# Sheet2.net
KiCad netlist of a schematic drawn in Altium Designer
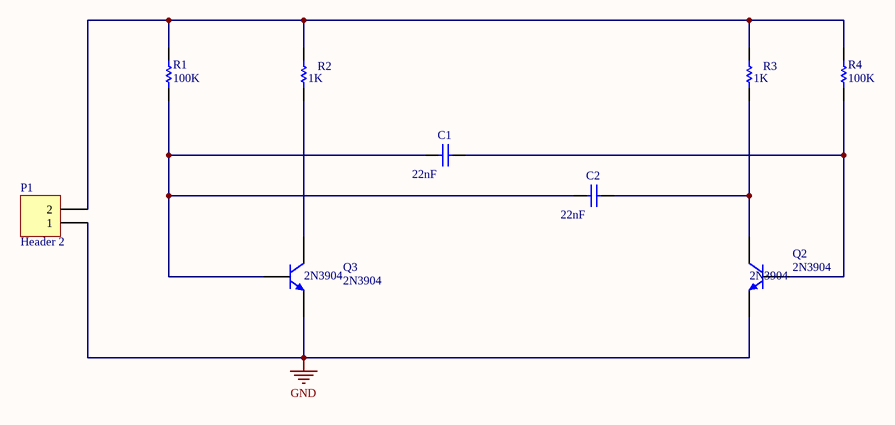
[diagram p0: Sheet2.SchDoc]

(export (version "E")
  (design (tool "Eeschema 10.0.6"))
  (components
    (comp (ref "C1")
      (value "22nF")
      (footprint "CAP1206")
      (description "TOTAL CAPACITOR SMD PACK")
      (fields (field (name "DESIGNER") "Abbas Basereh"))
      (libsource (lib "Altium") (part "CAP SMD PACKAGE"))
    )
    (comp (ref "C2")
      (value "22nF")
      (footprint "CAP1206")
      (description "TOTAL CAPACITOR SMD PACK")
      (fields (field (name "DESIGNER") "Abbas Basereh"))
      (libsource (lib "Altium") (part "CAP SMD PACKAGE"))
    )
    (comp (ref "P1")
      (value "Header 2")
      (footprint "HDR1X2")
      (description "Header, 2-Pin")
      (fields (field (name "PUBLISHER") "Altium Limited"))
      (libsource (lib "Altium") (part "Header 2"))
    )
    (comp (ref "Q2")
      (value "2N3904")
      (footprint "2N3904")
      (description "NPN Transistor")
      (libsource (lib "Altium") (part "2N3904"))
    )
    (comp (ref "Q3")
      (value "2N3904")
      (footprint "2N3904")
      (description "NPN Transistor")
      (libsource (lib "Altium") (part "2N3904"))
    )
    (comp (ref "R1")
      (value "100K")
      (footprint "RES1206")
      (description "TOTAL SMD RESISTOR PACK")
      (fields (field (name "DESIGNER") "Abbas Basereh"))
      (libsource (lib "Altium") (part "RES SMD PACKAGE"))
    )
    (comp (ref "R2")
      (value "1K")
      (footprint "RES1206")
      (description "TOTAL SMD RESISTOR PACK")
      (fields (field (name "DESIGNER") "Abbas Basereh"))
      (libsource (lib "Altium") (part "RES SMD PACKAGE"))
    )
    (comp (ref "R3")
      (value "1K")
      (footprint "RES1206")
      (description "TOTAL SMD RESISTOR PACK")
      (fields (field (name "DESIGNER") "Abbas Basereh"))
      (libsource (lib "Altium") (part "RES SMD PACKAGE"))
    )
    (comp (ref "R4")
      (value "100K")
      (footprint "RES1206")
      (description "TOTAL SMD RESISTOR PACK")
      (fields (field (name "DESIGNER") "Abbas Basereh"))
      (libsource (lib "Altium") (part "RES SMD PACKAGE"))
    )
  )
  (nets
    (net (code "1") (name "GND") (class "Default")
      (node (ref "P1") (pin "1") (pinfunction "1_1") (pintype "passive"))
      (node (ref "Q2") (pin "1") (pinfunction "E_1") (pintype "passive"))
      (node (ref "Q3") (pin "1") (pinfunction "E_1") (pintype "passive"))
    )
    (net (code "2") (name "Net-(P1-Pad2)") (class "Default")
      (node (ref "P1") (pin "2") (pinfunction "2_2") (pintype "passive"))
      (node (ref "R1") (pin "2") (pinfunction "2_2") (pintype "passive"))
      (node (ref "R2") (pin "2") (pinfunction "2_2") (pintype "passive"))
      (node (ref "R3") (pin "2") (pinfunction "2_2") (pintype "passive"))
      (node (ref "R4") (pin "2") (pinfunction "2_2") (pintype "passive"))
    )
    (net (code "3") (name "Net-(Q2-B)") (class "Default")
      (node (ref "C1") (pin "2") (pinfunction "2_2") (pintype "passive"))
      (node (ref "Q2") (pin "2") (pinfunction "B_2") (pintype "passive"))
      (node (ref "R4") (pin "1") (pinfunction "1_1") (pintype "passive"))
    )
    (net (code "4") (name "Net-(Q2-C)") (class "Default")
      (node (ref "C2") (pin "2") (pinfunction "2_2") (pintype "passive"))
      (node (ref "Q2") (pin "3") (pinfunction "C_3") (pintype "passive"))
      (node (ref "R3") (pin "1") (pinfunction "1_1") (pintype "passive"))
    )
    (net (code "5") (name "Net-(Q3-B)") (class "Default")
      (node (ref "C1") (pin "1") (pinfunction "1_1") (pintype "passive"))
      (node (ref "C2") (pin "1") (pinfunction "1_1") (pintype "passive"))
      (node (ref "Q3") (pin "2") (pinfunction "B_2") (pintype "passive"))
      (node (ref "R1") (pin "1") (pinfunction "1_1") (pintype "passive"))
    )
    (net (code "6") (name "Net-(Q3-C)") (class "Default")
      (node (ref "Q3") (pin "3") (pinfunction "C_3") (pintype "passive"))
      (node (ref "R2") (pin "1") (pinfunction "1_1") (pintype "passive"))
    )
  )
)
